# ChargePreAmplifer.net
KiCad netlist of a schematic drawn in Altium Designer
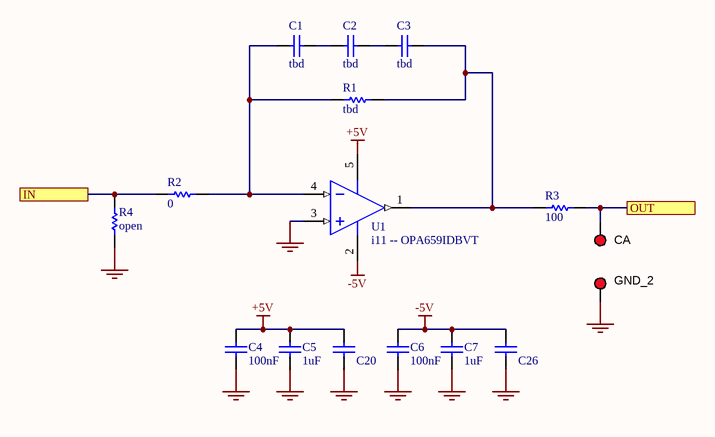
[diagram p0: ChargePreAmplifer.SchDoc]

(export (version "E")
  (design (tool "Eeschema 10.0.6"))
  (components
    (comp (ref "C1")
      (value "tbd")
      (footprint "CAPC0603(1608)100_N")
      (description "CAP 1uF 25V ±20% 0603 (1608 Metric) Thickness 1mm SMD")
      (fields (field (name "TOLERANCE") "Â±20%"))
      (libsource (lib "Altium Content Vault") (part "CAP"))
    )
    (comp (ref "C2")
      (value "tbd")
      (footprint "CAPC0603(1608)100_N")
      (description "CAP 1uF 25V ±20% 0603 (1608 Metric) Thickness 1mm SMD")
      (fields (field (name "TOLERANCE") "Â±20%"))
      (libsource (lib "Altium Content Vault") (part "CAP"))
    )
    (comp (ref "C3")
      (value "tbd")
      (footprint "CAPC0603(1608)100_N")
      (description "CAP 1uF 25V ±20% 0603 (1608 Metric) Thickness 1mm SMD")
      (fields (field (name "TOLERANCE") "Â±20%"))
      (libsource (lib "Altium Content Vault") (part "CAP"))
    )
    (comp (ref "C4")
      (value "100nF")
      (footprint "CAPC0603(1608)100_N")
      (description "CAP 100nF 25V ±20% 0603 (1608 Metric) Thickness 1mm SMD")
      (fields (field (name "TOLERANCE") "Â±20%"))
      (libsource (lib "Altium Content Vault") (part "CAP"))
    )
    (comp (ref "C5")
      (value "1uF")
      (footprint "CAPC0603(1608)100_N")
      (description "CAP 1uF 25V ±20% 0603 (1608 Metric) Thickness 1mm SMD")
      (fields (field (name "TOLERANCE") "Â±20%"))
      (libsource (lib "Altium Content Vault") (part "CAP"))
    )
    (comp (ref "C6")
      (value "100nF")
      (footprint "CAPC0603(1608)100_N")
      (description "CAP 100nF 25V ±20% 0603 (1608 Metric) Thickness 1mm SMD")
      (fields (field (name "TOLERANCE") "Â±20%"))
      (libsource (lib "Altium Content Vault") (part "CAP"))
    )
    (comp (ref "C7")
      (value "1uF")
      (footprint "CAPC0603(1608)100_N")
      (description "CAP 1uF 25V ±20% 0603 (1608 Metric) Thickness 1mm SMD")
      (fields (field (name "TOLERANCE") "Â±20%"))
      (libsource (lib "Altium Content Vault") (part "CAP"))
    )
    (comp (ref "C20")
      (value "10uF X7R 10V 0805")
      (footprint "CAPC0805(2012)145_N")
      (fields (field (name "TOLERANCE") "Â±10%"))
      (libsource (lib "Altium Content Vault") (part "CAP"))
    )
    (comp (ref "C26")
      (value "10uF X7R 10V 0805")
      (footprint "CAPC0805(2012)145_N")
      (fields (field (name "TOLERANCE") "Â±10%"))
      (libsource (lib "Altium Content Vault") (part "CAP"))
    )
    (comp (ref "CA")
      (value "5010")
      (footprint "KSTN-5010_V")
      (description "Test Point, Red, Through Hole, RoHS, Bulk")
      (libsource (lib "Altium Content Vault") (part "TESTPOINT_RED"))
    )
    (comp (ref "GND_2")
      (value "5010")
      (footprint "KSTN-5010_V")
      (description "Test Point, Red, Through Hole, RoHS, Bulk")
      (libsource (lib "Altium Content Vault") (part "TESTPOINT_RED"))
    )
    (comp (ref "R1")
      (value "tbd")
      (footprint "RESC0603(1608)_N")
      (description "100R 0.1W 1% 0603 (1608 Metric)  SMD")
      (fields (field (name "TOLERANCE") "1 %") (field (name "POWER") "0.1 W"))
      (libsource (lib "Altium Content Vault") (part "RES"))
    )
    (comp (ref "R2")
      (value "0")
      (footprint "RESC0603(1608)_N")
      (description "100R 0.1W 1% 0603 (1608 Metric)  SMD")
      (fields (field (name "TOLERANCE") "1 %") (field (name "POWER") "0.1 W"))
      (libsource (lib "Altium Content Vault") (part "RES"))
    )
    (comp (ref "R3")
      (value "100")
      (footprint "RESC0603(1608)_L")
      (description "100R 0.1W 1% 0603 (1608 Metric)  SMD")
      (fields (field (name "TOLERANCE") "1 %") (field (name "POWER") "0.1 W"))
      (libsource (lib "Altium Content Vault") (part "RES"))
    )
    (comp (ref "R4")
      (value "open")
      (footprint "RESC0603(1608)_N")
      (description "100R 0.1W 1% 0603 (1608 Metric)  SMD")
      (fields (field (name "TOLERANCE") "1 %") (field (name "POWER") "0.1 W"))
      (libsource (lib "Altium Content Vault") (part "RES"))
    )
    (comp (ref "U1")
      (value "i11 -- OPA659IDBVT")
      (footprint "TI-DBV5_L")
      (fields (field (name "MANUFACTURER") "Texas Instruments") (field (name "PARTNUMBER") "OPA659IDBVT"))
      (libsource (lib "Altium Content Vault") (part "TI-AMP-S3-2-DBV5_A"))
    )
  )
  (nets
    (net (code "1") (name "+5V") (class "Default")
      (node (ref "C20") (pin "2") (pinfunction "2_2") (pintype "passive"))
      (node (ref "C4") (pin "2") (pinfunction "2_2") (pintype "passive"))
      (node (ref "C5") (pin "2") (pinfunction "2_2") (pintype "passive"))
      (node (ref "U1") (pin "5") (pinfunction "VS+_5") (pintype "power_in"))
    )
    (net (code "2") (name "-5V") (class "Default")
      (node (ref "C26") (pin "2") (pinfunction "2_2") (pintype "passive"))
      (node (ref "C6") (pin "2") (pinfunction "2_2") (pintype "passive"))
      (node (ref "C7") (pin "2") (pinfunction "2_2") (pintype "passive"))
      (node (ref "U1") (pin "2") (pinfunction "VS-_2") (pintype "power_in"))
    )
    (net (code "3") (name "/IN") (class "Default")
      (node (ref "R2") (pin "1") (pinfunction "1_1") (pintype "passive"))
      (node (ref "R4") (pin "2") (pinfunction "2_2") (pintype "passive"))
    )
    (net (code "4") (name "/OUT") (class "Default")
      (node (ref "CA") (pin "1") (pinfunction "1_1") (pintype "passive"))
      (node (ref "R3") (pin "2") (pinfunction "2_2") (pintype "passive"))
    )
    (net (code "5") (name "GND") (class "Default")
      (node (ref "C20") (pin "1") (pinfunction "1_1") (pintype "passive"))
      (node (ref "C26") (pin "1") (pinfunction "1_1") (pintype "passive"))
      (node (ref "C4") (pin "1") (pinfunction "1_1") (pintype "passive"))
      (node (ref "C5") (pin "1") (pinfunction "1_1") (pintype "passive"))
      (node (ref "C6") (pin "1") (pinfunction "1_1") (pintype "passive"))
      (node (ref "C7") (pin "1") (pinfunction "1_1") (pintype "passive"))
      (node (ref "GND_2") (pin "1") (pinfunction "1_1") (pintype "passive"))
      (node (ref "R4") (pin "1") (pinfunction "1_1") (pintype "passive"))
      (node (ref "U1") (pin "3") (pinfunction "IN+_3") (pintype "input"))
    )
    (net (code "6") (name "Net-(C1-Pad1)") (class "Default")
      (node (ref "C1") (pin "1") (pinfunction "1_1") (pintype "passive"))
      (node (ref "C2") (pin "2") (pinfunction "2_2") (pintype "passive"))
    )
    (net (code "7") (name "Net-(C2-Pad1)") (class "Default")
      (node (ref "C2") (pin "1") (pinfunction "1_1") (pintype "passive"))
      (node (ref "C3") (pin "2") (pinfunction "2_2") (pintype "passive"))
    )
    (net (code "8") (name "Net-(U1-IN-)") (class "Default")
      (node (ref "C1") (pin "2") (pinfunction "2_2") (pintype "passive"))
      (node (ref "R1") (pin "1") (pinfunction "1_1") (pintype "passive"))
      (node (ref "R2") (pin "2") (pinfunction "2_2") (pintype "passive"))
      (node (ref "U1") (pin "4") (pinfunction "IN-_4") (pintype "input"))
    )
    (net (code "9") (name "Net-(U1-OUT)") (class "Default")
      (node (ref "C3") (pin "1") (pinfunction "1_1") (pintype "passive"))
      (node (ref "R1") (pin "2") (pinfunction "2_2") (pintype "passive"))
      (node (ref "R3") (pin "1") (pinfunction "1_1") (pintype "passive"))
      (node (ref "U1") (pin "1") (pinfunction "OUT_1") (pintype "output"))
    )
  )
)
